# GaugeRev2.net
KiCad netlist of a schematic drawn in EAGLE
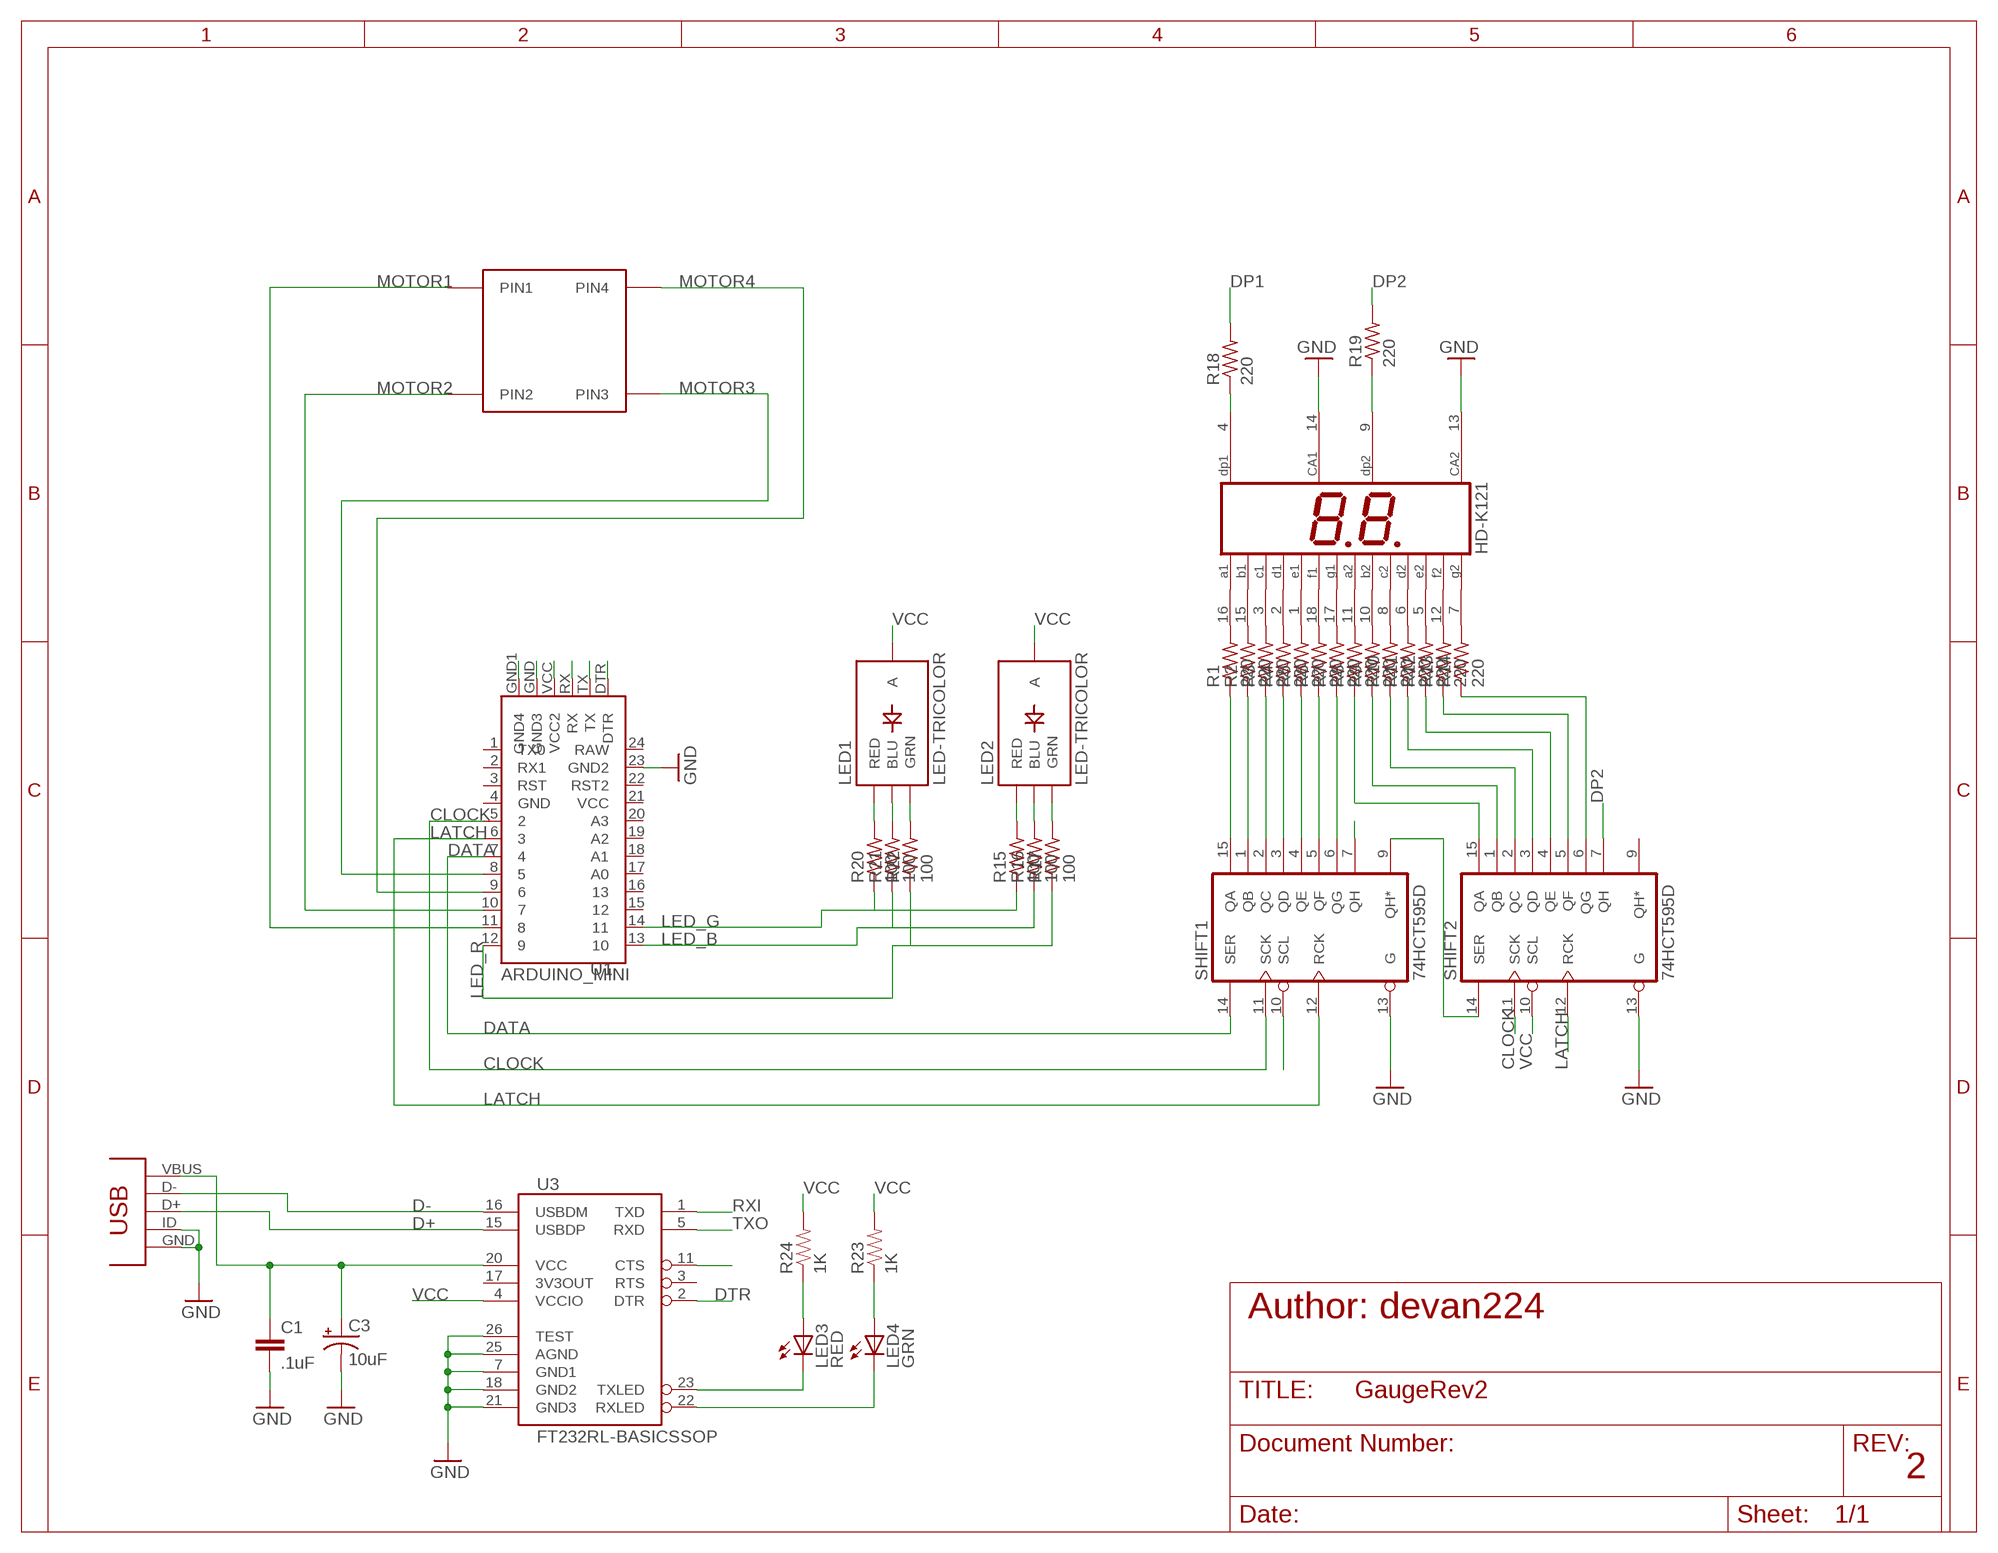
[diagram p0: schematic, sheet 1]

(export (version "E")
  (design (tool "Eeschema 10.0.6"))
  (components
    (comp (ref "C1")
      (value ".1uF")
      (footprint "eagle-import:1210")
      (libsource (lib "eagle-import") (part "CAP1210"))
    )
    (comp (ref "C3")
      (value "10uF")
      (footprint "eagle-import:EIA3216-KIT")
      (libsource (lib "eagle-import") (part "CAP_POL1206-KIT"))
    )
    (comp (ref "DIS2")
      (value "HD-K121")
      (footprint "eagle-import:HDSP-R")
      (libsource (lib "eagle-import") (part "HD-K121"))
    )
    (comp (ref "LED1")
      (value "LED-TRICOLOR")
      (footprint "eagle-import:LED-TRICOLOR-SMD")
      (libsource (lib "eagle-import") (part "LED-TRICOLOR"))
    )
    (comp (ref "LED2")
      (value "LED-TRICOLOR")
      (footprint "eagle-import:LED-TRICOLOR-SMD")
      (libsource (lib "eagle-import") (part "LED-TRICOLOR"))
    )
    (comp (ref "LED3")
      (value "RED")
      (footprint "eagle-import:LED-1206")
      (libsource (lib "eagle-import") (part "LED1206"))
    )
    (comp (ref "LED4")
      (value "GRN")
      (footprint "eagle-import:LED-1206")
      (libsource (lib "eagle-import") (part "LED1206"))
    )
    (comp (ref "R1")
      (value "220")
      (footprint "eagle-import:R1206")
      (libsource (lib "eagle-import") (part "R-US_R1206"))
    )
    (comp (ref "R2")
      (value "220")
      (footprint "eagle-import:R1206")
      (libsource (lib "eagle-import") (part "R-US_R1206"))
    )
    (comp (ref "R3")
      (value "220")
      (footprint "eagle-import:R1206")
      (libsource (lib "eagle-import") (part "R-US_R1206"))
    )
    (comp (ref "R4")
      (value "220")
      (footprint "eagle-import:R1206")
      (libsource (lib "eagle-import") (part "R-US_R1206"))
    )
    (comp (ref "R5")
      (value "220")
      (footprint "eagle-import:R1206")
      (libsource (lib "eagle-import") (part "R-US_R1206"))
    )
    (comp (ref "R6")
      (value "220")
      (footprint "eagle-import:R1206")
      (libsource (lib "eagle-import") (part "R-US_R1206"))
    )
    (comp (ref "R7")
      (value "220")
      (footprint "eagle-import:R1206")
      (libsource (lib "eagle-import") (part "R-US_R1206"))
    )
    (comp (ref "R8")
      (value "220")
      (footprint "eagle-import:R1206")
      (libsource (lib "eagle-import") (part "R-US_R1206"))
    )
    (comp (ref "R9")
      (value "220")
      (footprint "eagle-import:R1206")
      (libsource (lib "eagle-import") (part "R-US_R1206"))
    )
    (comp (ref "R10")
      (value "220")
      (footprint "eagle-import:R1206")
      (libsource (lib "eagle-import") (part "R-US_R1206"))
    )
    (comp (ref "R11")
      (value "220")
      (footprint "eagle-import:R1206")
      (libsource (lib "eagle-import") (part "R-US_R1206"))
    )
    (comp (ref "R12")
      (value "220")
      (footprint "eagle-import:R1206")
      (libsource (lib "eagle-import") (part "R-US_R1206"))
    )
    (comp (ref "R13")
      (value "220")
      (footprint "eagle-import:R1206")
      (libsource (lib "eagle-import") (part "R-US_R1206"))
    )
    (comp (ref "R14")
      (value "220")
      (footprint "eagle-import:R1206")
      (libsource (lib "eagle-import") (part "R-US_R1206"))
    )
    (comp (ref "R15")
      (value "100")
      (footprint "eagle-import:R1206")
      (libsource (lib "eagle-import") (part "R-US_R1206"))
    )
    (comp (ref "R16")
      (value "100")
      (footprint "eagle-import:R1206")
      (libsource (lib "eagle-import") (part "R-US_R1206"))
    )
    (comp (ref "R17")
      (value "100")
      (footprint "eagle-import:R1206")
      (libsource (lib "eagle-import") (part "R-US_R1206"))
    )
    (comp (ref "R18")
      (value "220")
      (footprint "eagle-import:R1206")
      (libsource (lib "eagle-import") (part "R-US_R1206"))
    )
    (comp (ref "R19")
      (value "220")
      (footprint "eagle-import:R1206")
      (libsource (lib "eagle-import") (part "R-US_R1206"))
    )
    (comp (ref "R20")
      (value "100")
      (footprint "eagle-import:R1206")
      (libsource (lib "eagle-import") (part "R-US_R1206"))
    )
    (comp (ref "R21")
      (value "100")
      (footprint "eagle-import:R1206")
      (libsource (lib "eagle-import") (part "R-US_R1206"))
    )
    (comp (ref "R22")
      (value "100")
      (footprint "eagle-import:R1206")
      (libsource (lib "eagle-import") (part "R-US_R1206"))
    )
    (comp (ref "R23")
      (value "1K")
      (footprint "eagle-import:1206")
      (libsource (lib "eagle-import") (part "RESISTOR1206"))
    )
    (comp (ref "R24")
      (value "1K")
      (footprint "eagle-import:1206")
      (libsource (lib "eagle-import") (part "RESISTOR1206"))
    )
    (comp (ref "SHIFT1")
      (value "74HCT595D")
      (footprint "eagle-import:SO16")
      (libsource (lib "eagle-import") (part "74595DHCT"))
    )
    (comp (ref "SHIFT2")
      (value "74HCT595D")
      (footprint "eagle-import:SO16")
      (libsource (lib "eagle-import") (part "74595DHCT"))
    )
    (comp (ref "U$1")
      (value "USB-MINI-VERT")
      (footprint "eagle-import:USB-MINI-VERT")
      (libsource (lib "eagle-import") (part "USB-MINI-VERT"))
    )
    (comp (ref "U1")
      (value "ARDUINO_MINI")
      (footprint "eagle-import:ARDUINO_MINI")
      (libsource (lib "eagle-import") (part "ARDUINO_MINI"))
    )
    (comp (ref "U2")
      (value "VID29")
      (footprint "eagle-import:VID29")
      (libsource (lib "eagle-import") (part "VID29"))
    )
    (comp (ref "U3")
      (value "FT232RL-BASICSSOP")
      (footprint "eagle-import:SSOP28DB")
      (libsource (lib "eagle-import") (part "FT232RL-BASICSSOP"))
    )
  )
  (nets
    (net (code "1") (name "/CLOCK") (class "Default")
      (node (ref "SHIFT1") (pin "11") (pinfunction "SCK_11") (pintype "input"))
      (node (ref "SHIFT2") (pin "11") (pinfunction "SCK_11") (pintype "input"))
      (node (ref "U1") (pin "5") (pinfunction "2_5") (pintype "bidirectional"))
    )
    (net (code "2") (name "/D+") (class "Default")
      (node (ref "U$1") (pin "D+") (pinfunction "D+_D+") (pintype "bidirectional"))
      (node (ref "U3") (pin "15") (pinfunction "USBDP_15") (pintype "bidirectional"))
    )
    (net (code "3") (name "/D-") (class "Default")
      (node (ref "U$1") (pin "D-") (pinfunction "D-_D-") (pintype "bidirectional"))
      (node (ref "U3") (pin "16") (pinfunction "USBDM_16") (pintype "bidirectional"))
    )
    (net (code "4") (name "/DATA") (class "Default")
      (node (ref "SHIFT1") (pin "14") (pinfunction "SER_14") (pintype "input"))
      (node (ref "U1") (pin "7") (pinfunction "4_7") (pintype "bidirectional"))
    )
    (net (code "5") (name "/DP1") (class "Default")
      (node (ref "R18") (pin "2") (pinfunction "2_2") (pintype "passive"))
      (node (ref "SHIFT1") (pin "7") (pinfunction "QH_7") (pintype "tri_state"))
    )
    (net (code "6") (name "/DP2") (class "Default")
      (node (ref "R19") (pin "2") (pinfunction "2_2") (pintype "passive"))
      (node (ref "SHIFT2") (pin "7") (pinfunction "QH_7") (pintype "tri_state"))
    )
    (net (code "7") (name "/DTR") (class "Default")
      (node (ref "U1") (pin "DTR") (pinfunction "DTR_DTR") (pintype "bidirectional"))
      (node (ref "U3") (pin "2") (pinfunction "DTR_2") (pintype "bidirectional"))
    )
    (net (code "8") (name "/LATCH") (class "Default")
      (node (ref "SHIFT1") (pin "12") (pinfunction "RCK_12") (pintype "input"))
      (node (ref "SHIFT2") (pin "12") (pinfunction "RCK_12") (pintype "input"))
      (node (ref "U1") (pin "6") (pinfunction "3_6") (pintype "bidirectional"))
    )
    (net (code "9") (name "/LED_B") (class "Default")
      (node (ref "R16") (pin "1") (pinfunction "1_1") (pintype "passive"))
      (node (ref "R21") (pin "1") (pinfunction "1_1") (pintype "passive"))
      (node (ref "U1") (pin "13") (pinfunction "10_13") (pintype "bidirectional"))
    )
    (net (code "10") (name "/LED_G") (class "Default")
      (node (ref "R15") (pin "1") (pinfunction "1_1") (pintype "passive"))
      (node (ref "R20") (pin "1") (pinfunction "1_1") (pintype "passive"))
      (node (ref "U1") (pin "14") (pinfunction "11_14") (pintype "bidirectional"))
    )
    (net (code "11") (name "/LED_R") (class "Default")
      (node (ref "R17") (pin "1") (pinfunction "1_1") (pintype "passive"))
      (node (ref "R22") (pin "1") (pinfunction "1_1") (pintype "passive"))
      (node (ref "U1") (pin "12") (pinfunction "9_12") (pintype "bidirectional"))
    )
    (net (code "12") (name "/MOTOR1") (class "Default")
      (node (ref "U1") (pin "11") (pinfunction "8_11") (pintype "bidirectional"))
      (node (ref "U2") (pin "PIN1") (pinfunction "PIN1_PIN1") (pintype "bidirectional"))
    )
    (net (code "13") (name "/MOTOR2") (class "Default")
      (node (ref "U1") (pin "10") (pinfunction "7_10") (pintype "bidirectional"))
      (node (ref "U2") (pin "PIN2") (pinfunction "PIN2_PIN2") (pintype "bidirectional"))
    )
    (net (code "14") (name "/MOTOR3") (class "Default")
      (node (ref "U1") (pin "8") (pinfunction "5_8") (pintype "bidirectional"))
      (node (ref "U2") (pin "PIN3") (pinfunction "PIN3_PIN3") (pintype "bidirectional"))
    )
    (net (code "15") (name "/MOTOR4") (class "Default")
      (node (ref "U1") (pin "9") (pinfunction "6_9") (pintype "bidirectional"))
      (node (ref "U2") (pin "PIN4") (pinfunction "PIN4_PIN4") (pintype "bidirectional"))
    )
    (net (code "16") (name "/RXI") (class "Default")
      (node (ref "U1") (pin "RX") (pinfunction "RX_RX") (pintype "bidirectional"))
      (node (ref "U3") (pin "1") (pinfunction "TXD_1") (pintype "output"))
    )
    (net (code "17") (name "/TXO") (class "Default")
      (node (ref "U1") (pin "TX") (pinfunction "TX_TX") (pintype "bidirectional"))
      (node (ref "U3") (pin "5") (pinfunction "RXD_5") (pintype "input"))
    )
    (net (code "18") (name "/VCC") (class "Default")
      (node (ref "LED1") (pin "A") (pinfunction "A_A") (pintype "bidirectional"))
      (node (ref "LED2") (pin "A") (pinfunction "A_A") (pintype "bidirectional"))
      (node (ref "R23") (pin "2") (pinfunction "2_2") (pintype "passive"))
      (node (ref "R24") (pin "2") (pinfunction "2_2") (pintype "passive"))
      (node (ref "SHIFT1") (pin "10") (pinfunction "SCL_10") (pintype "input"))
      (node (ref "SHIFT2") (pin "10") (pinfunction "SCL_10") (pintype "input"))
      (node (ref "U1") (pin "VCC") (pinfunction "VCC2_VCC") (pintype "bidirectional"))
      (node (ref "U3") (pin "4") (pinfunction "VCCIO_4") (pintype "power_in"))
    )
    (net (code "19") (name "GND") (class "Default")
      (node (ref "C1") (pin "2") (pinfunction "2_2") (pintype "passive"))
      (node (ref "C3") (pin "C") (pinfunction "-_C") (pintype "passive"))
      (node (ref "DIS2") (pin "13") (pinfunction "CA2_13") (pintype "passive"))
      (node (ref "DIS2") (pin "14") (pinfunction "CA1_14") (pintype "passive"))
      (node (ref "SHIFT1") (pin "13") (pinfunction "G_13") (pintype "input"))
      (node (ref "SHIFT2") (pin "13") (pinfunction "G_13") (pintype "input"))
      (node (ref "U$1") (pin "GND") (pinfunction "GND_GND") (pintype "bidirectional"))
      (node (ref "U$1") (pin "ID") (pinfunction "ID_ID") (pintype "bidirectional"))
      (node (ref "U1") (pin "23") (pinfunction "GND2_23") (pintype "bidirectional"))
      (node (ref "U1") (pin "GND") (pinfunction "GND3_GND") (pintype "bidirectional"))
      (node (ref "U1") (pin "GND1") (pinfunction "GND4_GND1") (pintype "bidirectional"))
      (node (ref "U3") (pin "11") (pinfunction "CTS_11") (pintype "bidirectional"))
      (node (ref "U3") (pin "18") (pinfunction "GND2_18") (pintype "power_in"))
      (node (ref "U3") (pin "21") (pinfunction "GND3_21") (pintype "power_in"))
      (node (ref "U3") (pin "25") (pinfunction "AGND_25") (pintype "power_in"))
      (node (ref "U3") (pin "26") (pinfunction "TEST_26") (pintype "input"))
      (node (ref "U3") (pin "7") (pinfunction "GND1_7") (pintype "power_in"))
    )
    (net (code "20") (name "Net-(C3-+)") (class "Default")
      (node (ref "C1") (pin "1") (pinfunction "1_1") (pintype "passive"))
      (node (ref "C3") (pin "A") (pinfunction "+_A") (pintype "passive"))
      (node (ref "U$1") (pin "VBUS") (pinfunction "VBUS_VBUS") (pintype "bidirectional"))
      (node (ref "U3") (pin "20") (pinfunction "VCC_20") (pintype "power_in"))
    )
    (net (code "21") (name "Net-(DIS2-A1)") (class "Default")
      (node (ref "DIS2") (pin "16") (pinfunction "A1_16") (pintype "passive"))
      (node (ref "R1") (pin "2") (pinfunction "2_2") (pintype "passive"))
    )
    (net (code "22") (name "Net-(DIS2-A2)") (class "Default")
      (node (ref "DIS2") (pin "11") (pinfunction "A2_11") (pintype "passive"))
      (node (ref "R8") (pin "2") (pinfunction "2_2") (pintype "passive"))
    )
    (net (code "23") (name "Net-(DIS2-B1)") (class "Default")
      (node (ref "DIS2") (pin "15") (pinfunction "B1_15") (pintype "passive"))
      (node (ref "R2") (pin "2") (pinfunction "2_2") (pintype "passive"))
    )
    (net (code "24") (name "Net-(DIS2-B2)") (class "Default")
      (node (ref "DIS2") (pin "10") (pinfunction "B2_10") (pintype "passive"))
      (node (ref "R9") (pin "2") (pinfunction "2_2") (pintype "passive"))
    )
    (net (code "25") (name "Net-(DIS2-C1)") (class "Default")
      (node (ref "DIS2") (pin "3") (pinfunction "C1_3") (pintype "passive"))
      (node (ref "R3") (pin "2") (pinfunction "2_2") (pintype "passive"))
    )
    (net (code "26") (name "Net-(DIS2-C2)") (class "Default")
      (node (ref "DIS2") (pin "8") (pinfunction "C2_8") (pintype "passive"))
      (node (ref "R10") (pin "2") (pinfunction "2_2") (pintype "passive"))
    )
    (net (code "27") (name "Net-(DIS2-D1)") (class "Default")
      (node (ref "DIS2") (pin "2") (pinfunction "D1_2") (pintype "passive"))
      (node (ref "R4") (pin "2") (pinfunction "2_2") (pintype "passive"))
    )
    (net (code "28") (name "Net-(DIS2-D2)") (class "Default")
      (node (ref "DIS2") (pin "6") (pinfunction "D2_6") (pintype "passive"))
      (node (ref "R11") (pin "2") (pinfunction "2_2") (pintype "passive"))
    )
    (net (code "29") (name "Net-(DIS2-DP1)") (class "Default")
      (node (ref "DIS2") (pin "4") (pinfunction "DP1_4") (pintype "passive"))
      (node (ref "R18") (pin "1") (pinfunction "1_1") (pintype "passive"))
    )
    (net (code "30") (name "Net-(DIS2-DP2)") (class "Default")
      (node (ref "DIS2") (pin "9") (pinfunction "DP2_9") (pintype "passive"))
      (node (ref "R19") (pin "1") (pinfunction "1_1") (pintype "passive"))
    )
    (net (code "31") (name "Net-(DIS2-E1)") (class "Default")
      (node (ref "DIS2") (pin "1") (pinfunction "E1_1") (pintype "passive"))
      (node (ref "R5") (pin "2") (pinfunction "2_2") (pintype "passive"))
    )
    (net (code "32") (name "Net-(DIS2-E2)") (class "Default")
      (node (ref "DIS2") (pin "5") (pinfunction "E2_5") (pintype "passive"))
      (node (ref "R12") (pin "2") (pinfunction "2_2") (pintype "passive"))
    )
    (net (code "33") (name "Net-(DIS2-F1)") (class "Default")
      (node (ref "DIS2") (pin "18") (pinfunction "F1_18") (pintype "passive"))
      (node (ref "R6") (pin "2") (pinfunction "2_2") (pintype "passive"))
    )
    (net (code "34") (name "Net-(DIS2-F2)") (class "Default")
      (node (ref "DIS2") (pin "12") (pinfunction "F2_12") (pintype "passive"))
      (node (ref "R13") (pin "2") (pinfunction "2_2") (pintype "passive"))
    )
    (net (code "35") (name "Net-(DIS2-G1)") (class "Default")
      (node (ref "DIS2") (pin "17") (pinfunction "G1_17") (pintype "passive"))
      (node (ref "R7") (pin "2") (pinfunction "2_2") (pintype "passive"))
    )
    (net (code "36") (name "Net-(DIS2-G2)") (class "Default")
      (node (ref "DIS2") (pin "7") (pinfunction "G2_7") (pintype "passive"))
      (node (ref "R14") (pin "2") (pinfunction "2_2") (pintype "passive"))
    )
    (net (code "37") (name "Net-(LED1-BLU)") (class "Default")
      (node (ref "LED1") (pin "B") (pinfunction "BLU_B") (pintype "bidirectional"))
      (node (ref "R21") (pin "2") (pinfunction "2_2") (pintype "passive"))
    )
    (net (code "38") (name "Net-(LED1-GRN)") (class "Default")
      (node (ref "LED1") (pin "G") (pinfunction "GRN_G") (pintype "bidirectional"))
      (node (ref "R22") (pin "2") (pinfunction "2_2") (pintype "passive"))
    )
    (net (code "39") (name "Net-(LED1-RED)") (class "Default")
      (node (ref "LED1") (pin "R") (pinfunction "RED_R") (pintype "bidirectional"))
      (node (ref "R20") (pin "2") (pinfunction "2_2") (pintype "passive"))
    )
    (net (code "40") (name "Net-(LED2-BLU)") (class "Default")
      (node (ref "LED2") (pin "B") (pinfunction "BLU_B") (pintype "bidirectional"))
      (node (ref "R16") (pin "2") (pinfunction "2_2") (pintype "passive"))
    )
    (net (code "41") (name "Net-(LED2-GRN)") (class "Default")
      (node (ref "LED2") (pin "G") (pinfunction "GRN_G") (pintype "bidirectional"))
      (node (ref "R17") (pin "2") (pinfunction "2_2") (pintype "passive"))
    )
    (net (code "42") (name "Net-(LED2-RED)") (class "Default")
      (node (ref "LED2") (pin "R") (pinfunction "RED_R") (pintype "bidirectional"))
      (node (ref "R15") (pin "2") (pinfunction "2_2") (pintype "passive"))
    )
    (net (code "43") (name "Net-(LED3-PadA)") (class "Default")
      (node (ref "LED3") (pin "A") (pinfunction "A_A") (pintype "passive"))
      (node (ref "R24") (pin "1") (pinfunction "1_1") (pintype "passive"))
    )
    (net (code "44") (name "Net-(LED4-PadA)") (class "Default")
      (node (ref "LED4") (pin "A") (pinfunction "A_A") (pintype "passive"))
      (node (ref "R23") (pin "1") (pinfunction "1_1") (pintype "passive"))
    )
    (net (code "45") (name "Net-(SHIFT1A-QA)") (class "Default")
      (node (ref "R1") (pin "1") (pinfunction "1_1") (pintype "passive"))
      (node (ref "SHIFT1") (pin "15") (pinfunction "QA_15") (pintype "tri_state"))
    )
    (net (code "46") (name "Net-(SHIFT1A-QB)") (class "Default")
      (node (ref "R2") (pin "1") (pinfunction "1_1") (pintype "passive"))
      (node (ref "SHIFT1") (pin "1") (pinfunction "QB_1") (pintype "tri_state"))
    )
    (net (code "47") (name "Net-(SHIFT1A-QC)") (class "Default")
      (node (ref "R3") (pin "1") (pinfunction "1_1") (pintype "passive"))
      (node (ref "SHIFT1") (pin "2") (pinfunction "QC_2") (pintype "tri_state"))
    )
    (net (code "48") (name "Net-(SHIFT1A-QD)") (class "Default")
      (node (ref "R4") (pin "1") (pinfunction "1_1") (pintype "passive"))
      (node (ref "SHIFT1") (pin "3") (pinfunction "QD_3") (pintype "tri_state"))
    )
    (net (code "49") (name "Net-(SHIFT1A-QE)") (class "Default")
      (node (ref "R5") (pin "1") (pinfunction "1_1") (pintype "passive"))
      (node (ref "SHIFT1") (pin "4") (pinfunction "QE_4") (pintype "tri_state"))
    )
    (net (code "50") (name "Net-(SHIFT1A-QF)") (class "Default")
      (node (ref "R6") (pin "1") (pinfunction "1_1") (pintype "passive"))
      (node (ref "SHIFT1") (pin "5") (pinfunction "QF_5") (pintype "tri_state"))
    )
    (net (code "51") (name "Net-(SHIFT1A-QG)") (class "Default")
      (node (ref "R7") (pin "1") (pinfunction "1_1") (pintype "passive"))
      (node (ref "SHIFT1") (pin "6") (pinfunction "QG_6") (pintype "tri_state"))
    )
    (net (code "52") (name "Net-(SHIFT1A-QH*)") (class "Default")
      (node (ref "SHIFT1") (pin "9") (pinfunction "QH*_9") (pintype "tri_state"))
      (node (ref "SHIFT2") (pin "14") (pinfunction "SER_14") (pintype "input"))
    )
    (net (code "53") (name "Net-(SHIFT2A-QA)") (class "Default")
      (node (ref "R8") (pin "1") (pinfunction "1_1") (pintype "passive"))
      (node (ref "SHIFT2") (pin "15") (pinfunction "QA_15") (pintype "tri_state"))
    )
    (net (code "54") (name "Net-(SHIFT2A-QB)") (class "Default")
      (node (ref "R9") (pin "1") (pinfunction "1_1") (pintype "passive"))
      (node (ref "SHIFT2") (pin "1") (pinfunction "QB_1") (pintype "tri_state"))
    )
    (net (code "55") (name "Net-(SHIFT2A-QC)") (class "Default")
      (node (ref "R10") (pin "1") (pinfunction "1_1") (pintype "passive"))
      (node (ref "SHIFT2") (pin "2") (pinfunction "QC_2") (pintype "tri_state"))
    )
    (net (code "56") (name "Net-(SHIFT2A-QD)") (class "Default")
      (node (ref "R11") (pin "1") (pinfunction "1_1") (pintype "passive"))
      (node (ref "SHIFT2") (pin "3") (pinfunction "QD_3") (pintype "tri_state"))
    )
    (net (code "57") (name "Net-(SHIFT2A-QE)") (class "Default")
      (node (ref "R12") (pin "1") (pinfunction "1_1") (pintype "passive"))
      (node (ref "SHIFT2") (pin "4") (pinfunction "QE_4") (pintype "tri_state"))
    )
    (net (code "58") (name "Net-(SHIFT2A-QF)") (class "Default")
      (node (ref "R13") (pin "1") (pinfunction "1_1") (pintype "passive"))
      (node (ref "SHIFT2") (pin "5") (pinfunction "QF_5") (pintype "tri_state"))
    )
    (net (code "59") (name "Net-(SHIFT2A-QG)") (class "Default")
      (node (ref "R14") (pin "1") (pinfunction "1_1") (pintype "passive"))
      (node (ref "SHIFT2") (pin "6") (pinfunction "QG_6") (pintype "tri_state"))
    )
    (net (code "60") (name "Net-(U3-RXLED)") (class "Default")
      (node (ref "LED4") (pin "C") (pinfunction "C_C") (pintype "passive"))
      (node (ref "U3") (pin "22") (pinfunction "RXLED_22") (pintype "bidirectional"))
    )
    (net (code "61") (name "Net-(U3-TXLED)") (class "Default")
      (node (ref "LED3") (pin "C") (pinfunction "C_C") (pintype "passive"))
      (node (ref "U3") (pin "23") (pinfunction "TXLED_23") (pintype "bidirectional"))
    )
    (net (code "62") (name "unconnected-(SHIFT2A-QH*-Pad9)") (class "Default")
      (node (ref "SHIFT2") (pin "9") (pinfunction "QH*_9") (pintype "tri_state"))
    )
    (net (code "63") (name "unconnected-(U1-12-Pad15)") (class "Default")
      (node (ref "U1") (pin "15") (pinfunction "12_15") (pintype "bidirectional"))
    )
    (net (code "64") (name "unconnected-(U1-13-Pad16)") (class "Default")
      (node (ref "U1") (pin "16") (pinfunction "13_16") (pintype "bidirectional"))
    )
    (net (code "65") (name "unconnected-(U1-A0-Pad17)") (class "Default")
      (node (ref "U1") (pin "17") (pinfunction "A0_17") (pintype "bidirectional"))
    )
    (net (code "66") (name "unconnected-(U1-A1-Pad18)") (class "Default")
      (node (ref "U1") (pin "18") (pinfunction "A1_18") (pintype "bidirectional"))
    )
    (net (code "67") (name "unconnected-(U1-A2-Pad19)") (class "Default")
      (node (ref "U1") (pin "19") (pinfunction "A2_19") (pintype "bidirectional"))
    )
    (net (code "68") (name "unconnected-(U1-A3-Pad20)") (class "Default")
      (node (ref "U1") (pin "20") (pinfunction "A3_20") (pintype "bidirectional"))
    )
    (net (code "69") (name "unconnected-(U1-GND-Pad4)") (class "Default")
      (node (ref "U1") (pin "4") (pinfunction "GND_4") (pintype "bidirectional"))
    )
    (net (code "70") (name "unconnected-(U1-RAW-Pad24)") (class "Default")
      (node (ref "U1") (pin "24") (pinfunction "RAW_24") (pintype "bidirectional"))
    )
    (net (code "71") (name "unconnected-(U1-RST-Pad3)") (class "Default")
      (node (ref "U1") (pin "3") (pinfunction "RST_3") (pintype "bidirectional"))
    )
    (net (code "72") (name "unconnected-(U1-RST2-Pad22)") (class "Default")
      (node (ref "U1") (pin "22") (pinfunction "RST2_22") (pintype "bidirectional"))
    )
    (net (code "73") (name "unconnected-(U1-RX1-Pad2)") (class "Default")
      (node (ref "U1") (pin "2") (pinfunction "RX1_2") (pintype "bidirectional"))
    )
    (net (code "74") (name "unconnected-(U1-TX0-Pad1)") (class "Default")
      (node (ref "U1") (pin "1") (pinfunction "TX0_1") (pintype "bidirectional"))
    )
    (net (code "75") (name "unconnected-(U1-VCC-Pad21)") (class "Default")
      (node (ref "U1") (pin "21") (pinfunction "VCC_21") (pintype "bidirectional"))
    )
    (net (code "76") (name "unconnected-(U3-3V3OUT-Pad17)") (class "Default")
      (node (ref "U3") (pin "17") (pinfunction "3V3OUT_17") (pintype "output"))
    )
    (net (code "77") (name "unconnected-(U3-RTS-Pad3)") (class "Default")
      (node (ref "U3") (pin "3") (pinfunction "RTS_3") (pintype "bidirectional"))
    )
  )
)
